# 4ButtonSwitch_Rev4_0.net
KiCad netlist of a schematic drawn in EAGLE
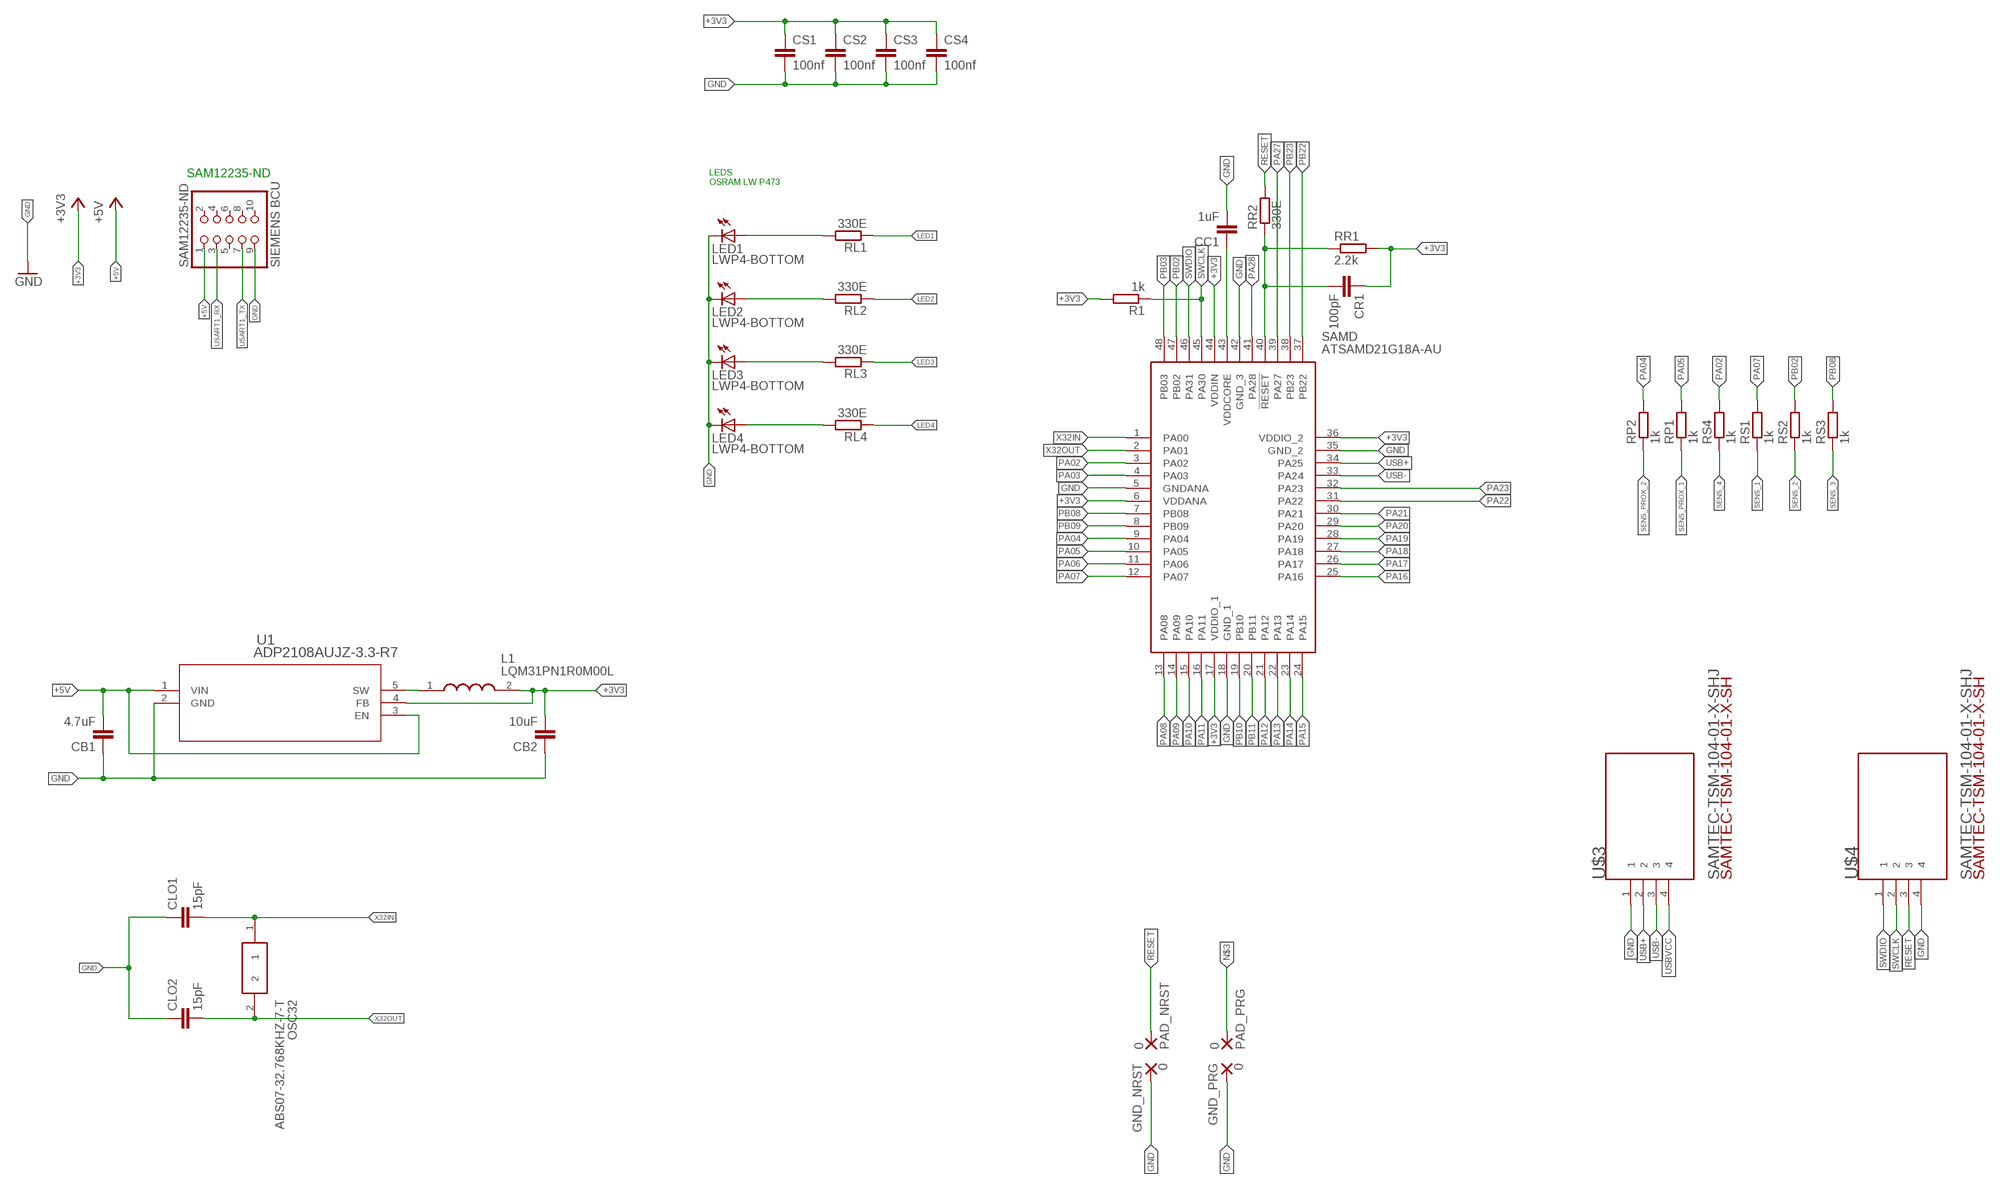
[diagram p0: schematic, sheet 1]

(export (version "E")
  (design (tool "Eeschema 10.0.6"))
  (components
    (comp (ref "CB1")
      (value "4.7uF")
      (footprint "eagle-import:C1206")
      (libsource (lib "eagle-import") (part "C-EUC1206"))
    )
    (comp (ref "CB2")
      (value "10uF")
      (footprint "eagle-import:C1206")
      (libsource (lib "eagle-import") (part "C-EUC1206"))
    )
    (comp (ref "CC1")
      (value "1uF")
      (footprint "eagle-import:C1206")
      (libsource (lib "eagle-import") (part "C-EUC1206"))
    )
    (comp (ref "CLO1")
      (value "15pF")
      (footprint "eagle-import:C1206")
      (libsource (lib "eagle-import") (part "C-EUC1206"))
    )
    (comp (ref "CLO2")
      (value "15pF")
      (footprint "eagle-import:C1206")
      (libsource (lib "eagle-import") (part "C-EUC1206"))
    )
    (comp (ref "CR1")
      (value "100pF")
      (footprint "eagle-import:C1206")
      (libsource (lib "eagle-import") (part "C-EUC1206"))
    )
    (comp (ref "CS1")
      (value "100nf")
      (footprint "eagle-import:C1206")
      (libsource (lib "eagle-import") (part "C-EUC1206"))
    )
    (comp (ref "CS2")
      (value "100nf")
      (footprint "eagle-import:C1206")
      (libsource (lib "eagle-import") (part "C-EUC1206"))
    )
    (comp (ref "CS3")
      (value "100nf")
      (footprint "eagle-import:C1206")
      (libsource (lib "eagle-import") (part "C-EUC1206"))
    )
    (comp (ref "CS4")
      (value "100nf")
      (footprint "eagle-import:C1206")
      (libsource (lib "eagle-import") (part "C-EUC1206"))
    )
    (comp (ref "GND_NRST")
      (value "0")
      (footprint "eagle-import:SMD2,54-5,08")
      (libsource (lib "eagle-import") (part "SMD5"))
    )
    (comp (ref "GND_PRG")
      (value "0")
      (footprint "eagle-import:SMD2,54-5,08")
      (libsource (lib "eagle-import") (part "SMD5"))
    )
    (comp (ref "L1")
      (value "LQM31PN1R0M00L")
      (footprint "eagle-import:INDC3216X95N")
      (fields (field (name "RS_PART_NUMBER") "1674189"))
      (libsource (lib "eagle-import") (part "LQM31PN1R0M00L"))
    )
    (comp (ref "LED1")
      (value "LWP4-BOTTOM")
      (footprint "eagle-import:P47F-BOTTOM")
      (libsource (lib "eagle-import") (part "P4-BOTTOMLW"))
    )
    (comp (ref "LED2")
      (value "LWP4-BOTTOM")
      (footprint "eagle-import:P47F-BOTTOM")
      (libsource (lib "eagle-import") (part "P4-BOTTOMLW"))
    )
    (comp (ref "LED3")
      (value "LWP4-BOTTOM")
      (footprint "eagle-import:P47F-BOTTOM")
      (libsource (lib "eagle-import") (part "P4-BOTTOMLW"))
    )
    (comp (ref "LED4")
      (value "LWP4-BOTTOM")
      (footprint "eagle-import:P47F-BOTTOM")
      (libsource (lib "eagle-import") (part "P4-BOTTOMLW"))
    )
    (comp (ref "OSC32")
      (value "ABS07-32.768KHZ-7-T")
      (footprint "eagle-import:ABS-07")
      (fields (field (name "RS_PART_NUMBER") "1712773P"))
      (libsource (lib "eagle-import") (part "ABS07-32.768KHZ-7-T"))
    )
    (comp (ref "PAD_NRST")
      (value "0")
      (footprint "eagle-import:SMD2,54-5,08")
      (libsource (lib "eagle-import") (part "SMD5"))
    )
    (comp (ref "PAD_PRG")
      (value "0")
      (footprint "eagle-import:SMD2,54-5,08")
      (libsource (lib "eagle-import") (part "SMD5"))
    )
    (comp (ref "R1")
      (value "1k")
      (footprint "eagle-import:R1206")
      (libsource (lib "eagle-import") (part "R-EU_R1206"))
    )
    (comp (ref "RL1")
      (value "330E")
      (footprint "eagle-import:R1206")
      (libsource (lib "eagle-import") (part "R-EU_R1206"))
    )
    (comp (ref "RL2")
      (value "330E")
      (footprint "eagle-import:R1206")
      (libsource (lib "eagle-import") (part "R-EU_R1206"))
    )
    (comp (ref "RL3")
      (value "330E")
      (footprint "eagle-import:R1206")
      (libsource (lib "eagle-import") (part "R-EU_R1206"))
    )
    (comp (ref "RL4")
      (value "330E")
      (footprint "eagle-import:R1206")
      (libsource (lib "eagle-import") (part "R-EU_R1206"))
    )
    (comp (ref "RP1")
      (value "1k")
      (footprint "eagle-import:R1206")
      (libsource (lib "eagle-import") (part "R-EU_R1206"))
    )
    (comp (ref "RP2")
      (value "1k")
      (footprint "eagle-import:R1206")
      (libsource (lib "eagle-import") (part "R-EU_R1206"))
    )
    (comp (ref "RR1")
      (value "2.2k")
      (footprint "eagle-import:R1206")
      (libsource (lib "eagle-import") (part "R-EU_R1206"))
    )
    (comp (ref "RR2")
      (value "330E")
      (footprint "eagle-import:R1206")
      (libsource (lib "eagle-import") (part "R-EU_R1206"))
    )
    (comp (ref "RS1")
      (value "1k")
      (footprint "eagle-import:R1206")
      (libsource (lib "eagle-import") (part "R-EU_R1206"))
    )
    (comp (ref "RS2")
      (value "1k")
      (footprint "eagle-import:R1206")
      (libsource (lib "eagle-import") (part "R-EU_R1206"))
    )
    (comp (ref "RS3")
      (value "1k")
      (footprint "eagle-import:R1206")
      (libsource (lib "eagle-import") (part "R-EU_R1206"))
    )
    (comp (ref "RS4")
      (value "1k")
      (footprint "eagle-import:R1206")
      (libsource (lib "eagle-import") (part "R-EU_R1206"))
    )
    (comp (ref "SAM12235-ND")
      (value "SIEMENS BCU")
      (footprint "eagle-import:2X05SMD")
      (libsource (lib "eagle-import") (part "PINHD-2X5_2.54-SMD"))
    )
    (comp (ref "SAMD")
      (value "ATSAMD21G18A-AU")
      (footprint "eagle-import:QFP50P900X900X120-48N")
      (fields (field (name "RS_PART_NUMBER") "1773799P"))
      (libsource (lib "eagle-import") (part "ATSAMD21G18A-AU"))
    )
    (comp (ref "U$3")
      (value "SAMTEC-TSM-104-01-X-SHJ")
      (footprint "eagle-import:SAMTEC-TSM-104-01-X-SH")
      (fields (field (name "MF") "Samtec") (field (name "MP") "TSM-104-01-T-SH"))
      (libsource (lib "eagle-import") (part "SAMTEC-TSM-104-01-X-SHJ"))
    )
    (comp (ref "U$4")
      (value "SAMTEC-TSM-104-01-X-SHJ")
      (footprint "eagle-import:SAMTEC-TSM-104-01-X-SH")
      (fields (field (name "MF") "Samtec") (field (name "MP") "TSM-104-01-T-SH"))
      (libsource (lib "eagle-import") (part "SAMTEC-TSM-104-01-X-SHJ"))
    )
    (comp (ref "U1")
      (value "ADP2108AUJZ-3.3-R7")
      (footprint "eagle-import:UJ_5")
      (fields (field (name "MANUFACTURER_PART_NUMBER") "ADP2108AUJZ3.3R7"))
      (libsource (lib "eagle-import") (part "ADP2108AUJZ-3.3-R7"))
    )
  )
  (nets
    (net (code "1") (name "+3V3") (class "Default")
      (node (ref "CB2") (pin "2") (pinfunction "2_2") (pintype "passive"))
      (node (ref "CR1") (pin "1") (pinfunction "1_1") (pintype "passive"))
      (node (ref "CS1") (pin "1") (pinfunction "1_1") (pintype "passive"))
      (node (ref "CS2") (pin "1") (pinfunction "1_1") (pintype "passive"))
      (node (ref "CS3") (pin "1") (pinfunction "1_1") (pintype "passive"))
      (node (ref "CS4") (pin "1") (pinfunction "1_1") (pintype "passive"))
      (node (ref "L1") (pin "2") (pinfunction "2_2") (pintype "bidirectional"))
      (node (ref "R1") (pin "2") (pinfunction "2_2") (pintype "passive"))
      (node (ref "RR1") (pin "2") (pinfunction "2_2") (pintype "passive"))
      (node (ref "SAMD") (pin "17") (pinfunction "VDDIO_1_17") (pintype "bidirectional"))
      (node (ref "SAMD") (pin "36") (pinfunction "VDDIO_2_36") (pintype "bidirectional"))
      (node (ref "SAMD") (pin "44") (pinfunction "VDDIN_44") (pintype "bidirectional"))
      (node (ref "SAMD") (pin "6") (pinfunction "VDDANA_6") (pintype "bidirectional"))
      (node (ref "U1") (pin "4") (pinfunction "FB_4") (pintype "passive"))
    )
    (net (code "2") (name "+5V") (class "Default")
      (node (ref "CB1") (pin "2") (pinfunction "2_2") (pintype "passive"))
      (node (ref "SAM12235-ND") (pin "1") (pinfunction "1_1") (pintype "passive"))
      (node (ref "U1") (pin "1") (pinfunction "VIN_1") (pintype "passive"))
      (node (ref "U1") (pin "3") (pinfunction "EN_3") (pintype "passive"))
    )
    (net (code "3") (name "GND") (class "Default")
      (node (ref "CB1") (pin "1") (pinfunction "1_1") (pintype "passive"))
      (node (ref "CB2") (pin "1") (pinfunction "1_1") (pintype "passive"))
      (node (ref "CC1") (pin "2") (pinfunction "2_2") (pintype "passive"))
      (node (ref "CLO1") (pin "1") (pinfunction "1_1") (pintype "passive"))
      (node (ref "CLO2") (pin "1") (pinfunction "1_1") (pintype "passive"))
      (node (ref "CS1") (pin "2") (pinfunction "2_2") (pintype "passive"))
      (node (ref "CS2") (pin "2") (pinfunction "2_2") (pintype "passive"))
      (node (ref "CS3") (pin "2") (pinfunction "2_2") (pintype "passive"))
      (node (ref "CS4") (pin "2") (pinfunction "2_2") (pintype "passive"))
      (node (ref "GND_NRST") (pin "1") (pinfunction "P_1") (pintype "passive"))
      (node (ref "GND_PRG") (pin "1") (pinfunction "P_1") (pintype "passive"))
      (node (ref "LED1") (pin "C") (pinfunction "C_C") (pintype "passive"))
      (node (ref "LED2") (pin "C") (pinfunction "C_C") (pintype "passive"))
      (node (ref "LED3") (pin "C") (pinfunction "C_C") (pintype "passive"))
      (node (ref "LED4") (pin "C") (pinfunction "C_C") (pintype "passive"))
      (node (ref "SAM12235-ND") (pin "9") (pinfunction "9_9") (pintype "passive"))
      (node (ref "SAMD") (pin "18") (pinfunction "GND_1_18") (pintype "bidirectional"))
      (node (ref "SAMD") (pin "35") (pinfunction "GND_2_35") (pintype "bidirectional"))
      (node (ref "SAMD") (pin "42") (pinfunction "GND_3_42") (pintype "bidirectional"))
      (node (ref "SAMD") (pin "5") (pinfunction "GNDANA_5") (pintype "bidirectional"))
      (node (ref "U$3") (pin "1") (pinfunction "1_1") (pintype "bidirectional"))
      (node (ref "U$4") (pin "4") (pinfunction "4_4") (pintype "bidirectional"))
      (node (ref "U1") (pin "2") (pinfunction "GND_2") (pintype "passive"))
    )
    (net (code "4") (name "LED1") (class "Default")
      (node (ref "RL1") (pin "1") (pinfunction "1_1") (pintype "passive"))
    )
    (net (code "5") (name "LED2") (class "Default")
      (node (ref "RL2") (pin "1") (pinfunction "1_1") (pintype "passive"))
    )
    (net (code "6") (name "LED3") (class "Default")
      (node (ref "RL3") (pin "1") (pinfunction "1_1") (pintype "passive"))
    )
    (net (code "7") (name "LED4") (class "Default")
      (node (ref "RL4") (pin "1") (pinfunction "1_1") (pintype "passive"))
    )
    (net (code "8") (name "N$3") (class "Default")
      (node (ref "PAD_PRG") (pin "1") (pinfunction "P_1") (pintype "passive"))
    )
    (net (code "9") (name "Net-(LED1-PadA)") (class "Default")
      (node (ref "LED1") (pin "A") (pinfunction "A_A") (pintype "passive"))
      (node (ref "RL1") (pin "2") (pinfunction "2_2") (pintype "passive"))
    )
    (net (code "10") (name "Net-(LED2-PadA)") (class "Default")
      (node (ref "LED2") (pin "A") (pinfunction "A_A") (pintype "passive"))
      (node (ref "RL2") (pin "2") (pinfunction "2_2") (pintype "passive"))
    )
    (net (code "11") (name "Net-(LED3-PadA)") (class "Default")
      (node (ref "LED3") (pin "A") (pinfunction "A_A") (pintype "passive"))
      (node (ref "RL3") (pin "2") (pinfunction "2_2") (pintype "passive"))
    )
    (net (code "12") (name "Net-(LED4-PadA)") (class "Default")
      (node (ref "LED4") (pin "A") (pinfunction "A_A") (pintype "passive"))
      (node (ref "RL4") (pin "2") (pinfunction "2_2") (pintype "passive"))
    )
    (net (code "13") (name "Net-(SAMD-VDDCORE)") (class "Default")
      (node (ref "CC1") (pin "1") (pinfunction "1_1") (pintype "passive"))
      (node (ref "SAMD") (pin "43") (pinfunction "VDDCORE_43") (pintype "bidirectional"))
    )
    (net (code "14") (name "Net-(SAMD-~{RESET})") (class "Default")
      (node (ref "CR1") (pin "2") (pinfunction "2_2") (pintype "passive"))
      (node (ref "RR1") (pin "1") (pinfunction "1_1") (pintype "passive"))
      (node (ref "RR2") (pin "1") (pinfunction "1_1") (pintype "passive"))
      (node (ref "SAMD") (pin "40") (pinfunction "~{RESET}_40") (pintype "bidirectional"))
    )
    (net (code "15") (name "Net-(U1-SW)") (class "Default")
      (node (ref "L1") (pin "1") (pinfunction "1_1") (pintype "bidirectional"))
      (node (ref "U1") (pin "5") (pinfunction "SW_5") (pintype "passive"))
    )
    (net (code "16") (name "PA02") (class "Default")
      (node (ref "RS4") (pin "2") (pinfunction "2_2") (pintype "passive"))
      (node (ref "SAMD") (pin "3") (pinfunction "PA02_3") (pintype "bidirectional"))
    )
    (net (code "17") (name "PA03") (class "Default")
      (node (ref "SAMD") (pin "4") (pinfunction "PA03_4") (pintype "bidirectional"))
    )
    (net (code "18") (name "PA04") (class "Default")
      (node (ref "RP2") (pin "2") (pinfunction "2_2") (pintype "passive"))
      (node (ref "SAMD") (pin "9") (pinfunction "PA04_9") (pintype "bidirectional"))
    )
    (net (code "19") (name "PA05") (class "Default")
      (node (ref "RP1") (pin "2") (pinfunction "2_2") (pintype "passive"))
      (node (ref "SAMD") (pin "10") (pinfunction "PA05_10") (pintype "bidirectional"))
    )
    (net (code "20") (name "PA06") (class "Default")
      (node (ref "SAMD") (pin "11") (pinfunction "PA06_11") (pintype "bidirectional"))
    )
    (net (code "21") (name "PA07") (class "Default")
      (node (ref "RS1") (pin "2") (pinfunction "2_2") (pintype "passive"))
      (node (ref "SAMD") (pin "12") (pinfunction "PA07_12") (pintype "bidirectional"))
    )
    (net (code "22") (name "PA08") (class "Default")
      (node (ref "SAMD") (pin "13") (pinfunction "PA08_13") (pintype "bidirectional"))
    )
    (net (code "23") (name "PA09") (class "Default")
      (node (ref "SAMD") (pin "14") (pinfunction "PA09_14") (pintype "bidirectional"))
    )
    (net (code "24") (name "PA10") (class "Default")
      (node (ref "SAMD") (pin "15") (pinfunction "PA10_15") (pintype "bidirectional"))
    )
    (net (code "25") (name "PA11") (class "Default")
      (node (ref "SAMD") (pin "16") (pinfunction "PA11_16") (pintype "bidirectional"))
    )
    (net (code "26") (name "PA12") (class "Default")
      (node (ref "SAMD") (pin "21") (pinfunction "PA12_21") (pintype "bidirectional"))
    )
    (net (code "27") (name "PA13") (class "Default")
      (node (ref "SAMD") (pin "22") (pinfunction "PA13_22") (pintype "bidirectional"))
    )
    (net (code "28") (name "PA14") (class "Default")
      (node (ref "SAMD") (pin "23") (pinfunction "PA14_23") (pintype "bidirectional"))
    )
    (net (code "29") (name "PA15") (class "Default")
      (node (ref "SAMD") (pin "24") (pinfunction "PA15_24") (pintype "bidirectional"))
    )
    (net (code "30") (name "PA16") (class "Default")
      (node (ref "SAMD") (pin "25") (pinfunction "PA16_25") (pintype "bidirectional"))
    )
    (net (code "31") (name "PA17") (class "Default")
      (node (ref "SAMD") (pin "26") (pinfunction "PA17_26") (pintype "bidirectional"))
    )
    (net (code "32") (name "PA18") (class "Default")
      (node (ref "SAMD") (pin "27") (pinfunction "PA18_27") (pintype "bidirectional"))
    )
    (net (code "33") (name "PA19") (class "Default")
      (node (ref "SAMD") (pin "28") (pinfunction "PA19_28") (pintype "bidirectional"))
    )
    (net (code "34") (name "PA20") (class "Default")
      (node (ref "SAMD") (pin "29") (pinfunction "PA20_29") (pintype "bidirectional"))
    )
    (net (code "35") (name "PA21") (class "Default")
      (node (ref "SAMD") (pin "30") (pinfunction "PA21_30") (pintype "bidirectional"))
    )
    (net (code "36") (name "PA22") (class "Default")
      (node (ref "SAMD") (pin "31") (pinfunction "PA22_31") (pintype "bidirectional"))
    )
    (net (code "37") (name "PA23") (class "Default")
      (node (ref "SAMD") (pin "32") (pinfunction "PA23_32") (pintype "bidirectional"))
    )
    (net (code "38") (name "PA27") (class "Default")
      (node (ref "SAMD") (pin "39") (pinfunction "PA27_39") (pintype "bidirectional"))
    )
    (net (code "39") (name "PA28") (class "Default")
      (node (ref "SAMD") (pin "41") (pinfunction "PA28_41") (pintype "bidirectional"))
    )
    (net (code "40") (name "PB02") (class "Default")
      (node (ref "RS2") (pin "2") (pinfunction "2_2") (pintype "passive"))
      (node (ref "SAMD") (pin "47") (pinfunction "PB02_47") (pintype "bidirectional"))
    )
    (net (code "41") (name "PB03") (class "Default")
      (node (ref "SAMD") (pin "48") (pinfunction "PB03_48") (pintype "bidirectional"))
    )
    (net (code "42") (name "PB08") (class "Default")
      (node (ref "RS3") (pin "2") (pinfunction "2_2") (pintype "passive"))
      (node (ref "SAMD") (pin "7") (pinfunction "PB08_7") (pintype "bidirectional"))
    )
    (net (code "43") (name "PB09") (class "Default")
      (node (ref "SAMD") (pin "8") (pinfunction "PB09_8") (pintype "bidirectional"))
    )
    (net (code "44") (name "PB10") (class "Default")
      (node (ref "SAMD") (pin "19") (pinfunction "PB10_19") (pintype "bidirectional"))
    )
    (net (code "45") (name "PB11") (class "Default")
      (node (ref "SAMD") (pin "20") (pinfunction "PB11_20") (pintype "bidirectional"))
    )
    (net (code "46") (name "PB22") (class "Default")
      (node (ref "SAMD") (pin "37") (pinfunction "PB22_37") (pintype "bidirectional"))
    )
    (net (code "47") (name "PB23") (class "Default")
      (node (ref "SAMD") (pin "38") (pinfunction "PB23_38") (pintype "bidirectional"))
    )
    (net (code "48") (name "RESET") (class "Default")
      (node (ref "PAD_NRST") (pin "1") (pinfunction "P_1") (pintype "passive"))
      (node (ref "RR2") (pin "2") (pinfunction "2_2") (pintype "passive"))
      (node (ref "U$4") (pin "3") (pinfunction "3_3") (pintype "bidirectional"))
    )
    (net (code "49") (name "SENS_1") (class "Default")
      (node (ref "RS1") (pin "1") (pinfunction "1_1") (pintype "passive"))
    )
    (net (code "50") (name "SENS_2") (class "Default")
      (node (ref "RS2") (pin "1") (pinfunction "1_1") (pintype "passive"))
    )
    (net (code "51") (name "SENS_3") (class "Default")
      (node (ref "RS3") (pin "1") (pinfunction "1_1") (pintype "passive"))
    )
    (net (code "52") (name "SENS_4") (class "Default")
      (node (ref "RS4") (pin "1") (pinfunction "1_1") (pintype "passive"))
    )
    (net (code "53") (name "SENS_PROX_1") (class "Default")
      (node (ref "RP1") (pin "1") (pinfunction "1_1") (pintype "passive"))
    )
    (net (code "54") (name "SENS_PROX_2") (class "Default")
      (node (ref "RP2") (pin "1") (pinfunction "1_1") (pintype "passive"))
    )
    (net (code "55") (name "SWCLK") (class "Default")
      (node (ref "R1") (pin "1") (pinfunction "1_1") (pintype "passive"))
      (node (ref "SAMD") (pin "45") (pinfunction "PA30_45") (pintype "bidirectional"))
      (node (ref "U$4") (pin "2") (pinfunction "2_2") (pintype "bidirectional"))
    )
    (net (code "56") (name "SWDIO") (class "Default")
      (node (ref "SAMD") (pin "46") (pinfunction "PA31_46") (pintype "bidirectional"))
      (node (ref "U$4") (pin "1") (pinfunction "1_1") (pintype "bidirectional"))
    )
    (net (code "57") (name "USART1_RX") (class "Default")
      (node (ref "SAM12235-ND") (pin "3") (pinfunction "3_3") (pintype "passive"))
    )
    (net (code "58") (name "USART1_TX") (class "Default")
      (node (ref "SAM12235-ND") (pin "7") (pinfunction "7_7") (pintype "passive"))
    )
    (net (code "59") (name "USB+") (class "Default")
      (node (ref "SAMD") (pin "34") (pinfunction "PA25_34") (pintype "bidirectional"))
      (node (ref "U$3") (pin "2") (pinfunction "2_2") (pintype "bidirectional"))
    )
    (net (code "60") (name "USB-") (class "Default")
      (node (ref "SAMD") (pin "33") (pinfunction "PA24_33") (pintype "bidirectional"))
      (node (ref "U$3") (pin "3") (pinfunction "3_3") (pintype "bidirectional"))
    )
    (net (code "61") (name "USBVCC") (class "Default")
      (node (ref "U$3") (pin "4") (pinfunction "4_4") (pintype "bidirectional"))
    )
    (net (code "62") (name "X32IN") (class "Default")
      (node (ref "CLO1") (pin "2") (pinfunction "2_2") (pintype "passive"))
      (node (ref "OSC32") (pin "1") (pinfunction "1_1") (pintype "bidirectional"))
      (node (ref "SAMD") (pin "1") (pinfunction "PA00_1") (pintype "bidirectional"))
    )
    (net (code "63") (name "X32OUT") (class "Default")
      (node (ref "CLO2") (pin "2") (pinfunction "2_2") (pintype "passive"))
      (node (ref "OSC32") (pin "2") (pinfunction "2_2") (pintype "bidirectional"))
      (node (ref "SAMD") (pin "2") (pinfunction "PA01_2") (pintype "bidirectional"))
    )
    (net (code "64") (name "unconnected-(SAM12235-ND-Pad2)") (class "Default")
      (node (ref "SAM12235-ND") (pin "2") (pinfunction "2_2") (pintype "passive"))
    )
    (net (code "65") (name "unconnected-(SAM12235-ND-Pad4)") (class "Default")
      (node (ref "SAM12235-ND") (pin "4") (pinfunction "4_4") (pintype "passive"))
    )
    (net (code "66") (name "unconnected-(SAM12235-ND-Pad5)") (class "Default")
      (node (ref "SAM12235-ND") (pin "5") (pinfunction "5_5") (pintype "passive"))
    )
    (net (code "67") (name "unconnected-(SAM12235-ND-Pad6)") (class "Default")
      (node (ref "SAM12235-ND") (pin "6") (pinfunction "6_6") (pintype "passive"))
    )
    (net (code "68") (name "unconnected-(SAM12235-ND-Pad8)") (class "Default")
      (node (ref "SAM12235-ND") (pin "8") (pinfunction "8_8") (pintype "passive"))
    )
    (net (code "69") (name "unconnected-(SAM12235-ND-Pad10)") (class "Default")
      (node (ref "SAM12235-ND") (pin "10") (pinfunction "10_10") (pintype "passive"))
    )
  )
)
